# Sheet1.net
KiCad netlist of a schematic drawn in Altium Designer
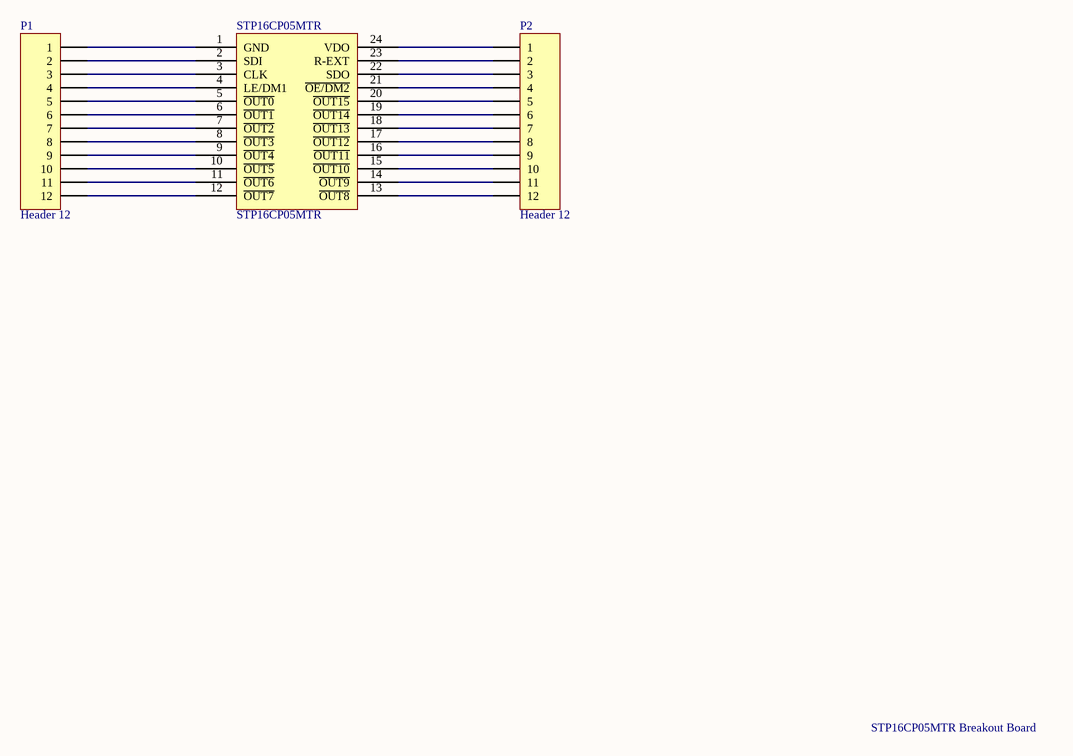
[diagram p0: Sheet1.SchDoc]

(export (version "E")
  (design (tool "Eeschema 10.0.6"))
  (components
    (comp (ref "P1")
      (value "Header 12")
      (footprint "HDR1X12")
      (description "Header, 12-Pin")
      (fields (field (name "PUBLISHER") "Altium Limited"))
      (libsource (lib "Miscellaneous Connectors") (part "Header 12"))
    )
    (comp (ref "P2")
      (value "Header 12")
      (footprint "HDR1X12")
      (description "Header, 12-Pin")
      (fields (field (name "PUBLISHER") "Altium Limited"))
      (libsource (lib "") (part "Header 12_1"))
    )
    (comp (ref "STP16CP05MTR")
      (value "STP16CP05MTR")
      (footprint "STP16CP05MTR-24N")
      (libsource (lib "STP16CP05MTR") (part "STP16CP05MTR"))
    )
  )
  (nets
    (net (code "1") (name "Net-(STP16CP05MTR-CLK)") (class "Default")
      (node (ref "P1") (pin "3") (pinfunction "3_3") (pintype "passive"))
      (node (ref "STP16CP05MTR") (pin "3") (pinfunction "CLK_3") (pintype "passive"))
    )
    (net (code "2") (name "Net-(STP16CP05MTR-GND)") (class "Default")
      (node (ref "P1") (pin "1") (pinfunction "1_1") (pintype "passive"))
      (node (ref "STP16CP05MTR") (pin "1") (pinfunction "GND_1") (pintype "passive"))
    )
    (net (code "3") (name "Net-(STP16CP05MTR-LE{slash}DM1)") (class "Default")
      (node (ref "P1") (pin "4") (pinfunction "4_4") (pintype "passive"))
      (node (ref "STP16CP05MTR") (pin "4") (pinfunction "LE/DM1_4") (pintype "passive"))
    )
    (net (code "4") (name "Net-(STP16CP05MTR-R-EXT)") (class "Default")
      (node (ref "P2") (pin "2") (pinfunction "2_2") (pintype "passive"))
      (node (ref "STP16CP05MTR") (pin "23") (pinfunction "R-EXT_23") (pintype "passive"))
    )
    (net (code "5") (name "Net-(STP16CP05MTR-SDI)") (class "Default")
      (node (ref "P1") (pin "2") (pinfunction "2_2") (pintype "passive"))
      (node (ref "STP16CP05MTR") (pin "2") (pinfunction "SDI_2") (pintype "passive"))
    )
    (net (code "6") (name "Net-(STP16CP05MTR-SDO)") (class "Default")
      (node (ref "P2") (pin "3") (pinfunction "3_3") (pintype "passive"))
      (node (ref "STP16CP05MTR") (pin "22") (pinfunction "SDO_22") (pintype "passive"))
    )
    (net (code "7") (name "Net-(STP16CP05MTR-VDO)") (class "Default")
      (node (ref "P2") (pin "1") (pinfunction "1_1") (pintype "passive"))
      (node (ref "STP16CP05MTR") (pin "24") (pinfunction "VDO_24") (pintype "passive"))
    )
    (net (code "8") (name "Net-(STP16CP05MTR-~{OE{slash}DM2})") (class "Default")
      (node (ref "P2") (pin "4") (pinfunction "4_4") (pintype "passive"))
      (node (ref "STP16CP05MTR") (pin "21") (pinfunction "~{OE/DM2}_21") (pintype "passive"))
    )
    (net (code "9") (name "Net-(STP16CP05MTR-~{OUT0})") (class "Default")
      (node (ref "P1") (pin "5") (pinfunction "5_5") (pintype "passive"))
      (node (ref "STP16CP05MTR") (pin "5") (pinfunction "~{OUT0}_5") (pintype "passive"))
    )
    (net (code "10") (name "Net-(STP16CP05MTR-~{OUT1})") (class "Default")
      (node (ref "P1") (pin "6") (pinfunction "6_6") (pintype "passive"))
      (node (ref "STP16CP05MTR") (pin "6") (pinfunction "~{OUT1}_6") (pintype "passive"))
    )
    (net (code "11") (name "Net-(STP16CP05MTR-~{OUT2})") (class "Default")
      (node (ref "P1") (pin "7") (pinfunction "7_7") (pintype "passive"))
      (node (ref "STP16CP05MTR") (pin "7") (pinfunction "~{OUT2}_7") (pintype "passive"))
    )
    (net (code "12") (name "Net-(STP16CP05MTR-~{OUT3})") (class "Default")
      (node (ref "P1") (pin "8") (pinfunction "8_8") (pintype "passive"))
      (node (ref "STP16CP05MTR") (pin "8") (pinfunction "~{OUT3}_8") (pintype "passive"))
    )
    (net (code "13") (name "Net-(STP16CP05MTR-~{OUT4})") (class "Default")
      (node (ref "P1") (pin "9") (pinfunction "9_9") (pintype "passive"))
      (node (ref "STP16CP05MTR") (pin "9") (pinfunction "~{OUT4}_9") (pintype "passive"))
    )
    (net (code "14") (name "Net-(STP16CP05MTR-~{OUT5})") (class "Default")
      (node (ref "P1") (pin "10") (pinfunction "10_10") (pintype "passive"))
      (node (ref "STP16CP05MTR") (pin "10") (pinfunction "~{OUT5}_10") (pintype "passive"))
    )
    (net (code "15") (name "Net-(STP16CP05MTR-~{OUT6})") (class "Default")
      (node (ref "P1") (pin "11") (pinfunction "11_11") (pintype "passive"))
      (node (ref "STP16CP05MTR") (pin "11") (pinfunction "~{OUT6}_11") (pintype "passive"))
    )
    (net (code "16") (name "Net-(STP16CP05MTR-~{OUT7})") (class "Default")
      (node (ref "P1") (pin "12") (pinfunction "12_12") (pintype "passive"))
      (node (ref "STP16CP05MTR") (pin "12") (pinfunction "~{OUT7}_12") (pintype "passive"))
    )
    (net (code "17") (name "Net-(STP16CP05MTR-~{OUT8})") (class "Default")
      (node (ref "P2") (pin "12") (pinfunction "12_12") (pintype "passive"))
      (node (ref "STP16CP05MTR") (pin "13") (pinfunction "~{OUT8}_13") (pintype "passive"))
    )
    (net (code "18") (name "Net-(STP16CP05MTR-~{OUT9})") (class "Default")
      (node (ref "P2") (pin "11") (pinfunction "11_11") (pintype "passive"))
      (node (ref "STP16CP05MTR") (pin "14") (pinfunction "~{OUT9}_14") (pintype "passive"))
    )
    (net (code "19") (name "Net-(STP16CP05MTR-~{OUT10})") (class "Default")
      (node (ref "P2") (pin "10") (pinfunction "10_10") (pintype "passive"))
      (node (ref "STP16CP05MTR") (pin "15") (pinfunction "~{OUT10}_15") (pintype "passive"))
    )
    (net (code "20") (name "Net-(STP16CP05MTR-~{OUT11})") (class "Default")
      (node (ref "P2") (pin "9") (pinfunction "9_9") (pintype "passive"))
      (node (ref "STP16CP05MTR") (pin "16") (pinfunction "~{OUT11}_16") (pintype "passive"))
    )
    (net (code "21") (name "Net-(STP16CP05MTR-~{OUT12})") (class "Default")
      (node (ref "P2") (pin "8") (pinfunction "8_8") (pintype "passive"))
      (node (ref "STP16CP05MTR") (pin "17") (pinfunction "~{OUT12}_17") (pintype "passive"))
    )
    (net (code "22") (name "Net-(STP16CP05MTR-~{OUT13})") (class "Default")
      (node (ref "P2") (pin "7") (pinfunction "7_7") (pintype "passive"))
      (node (ref "STP16CP05MTR") (pin "18") (pinfunction "~{OUT13}_18") (pintype "passive"))
    )
    (net (code "23") (name "Net-(STP16CP05MTR-~{OUT14})") (class "Default")
      (node (ref "P2") (pin "6") (pinfunction "6_6") (pintype "passive"))
      (node (ref "STP16CP05MTR") (pin "19") (pinfunction "~{OUT14}_19") (pintype "passive"))
    )
    (net (code "24") (name "Net-(STP16CP05MTR-~{OUT15})") (class "Default")
      (node (ref "P2") (pin "5") (pinfunction "5_5") (pintype "passive"))
      (node (ref "STP16CP05MTR") (pin "20") (pinfunction "~{OUT15}_20") (pintype "passive"))
    )
  )
)
